# H19R1_Backend.net
KiCad netlist of a schematic drawn in Altium Designer
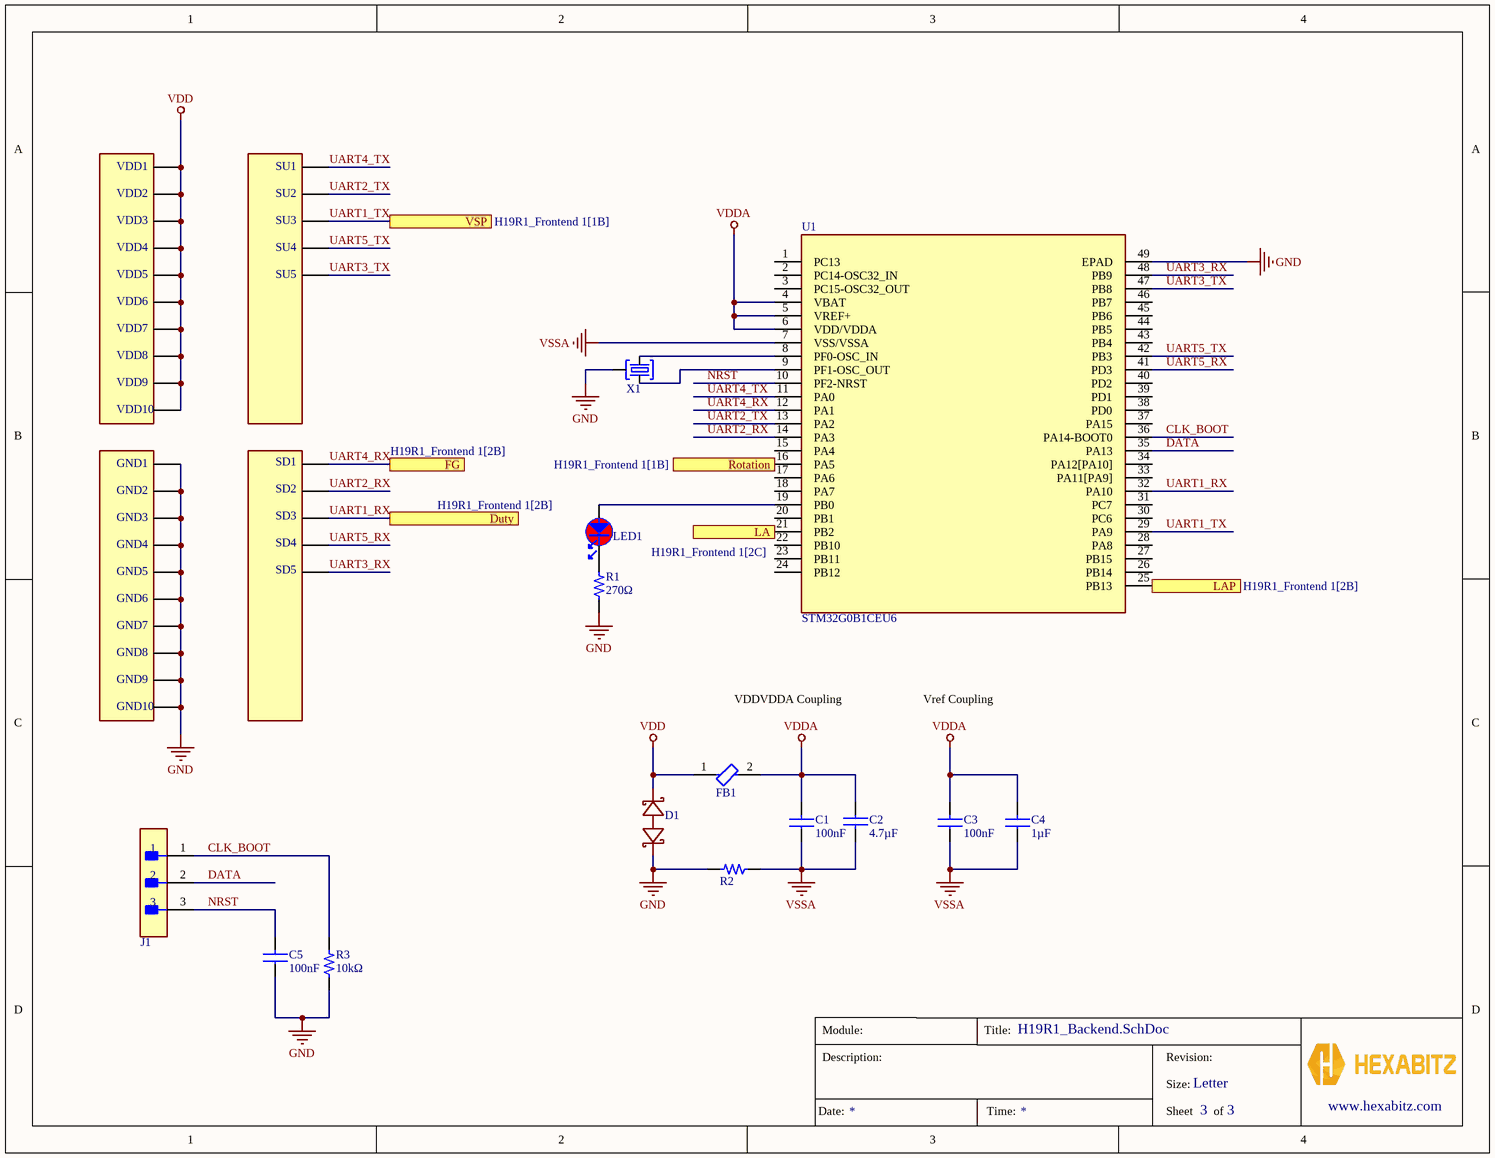
[diagram p0: H19R1_Backend.SchDoc]

(export (version "E")
  (design (tool "Eeschema 10.0.6"))
  (components
    (comp (ref "C1")
      (value "100nF")
      (footprint "C0603")
      (fields
        (field (name "MANUFACTURER") "Samsung Electro-Mechanics")
        (field (name "MANUFACTURER PART NUMBER") "CL10B104KA8NNNC")
        (field (name "TOLERANCE") "10%")
      )
      (libsource (lib "Hexabitz Altium Library") (part "generic Capacitor"))
    )
    (comp (ref "C2")
      (value "4.7µF")
      (footprint "C0805")
      (fields
        (field (name "MANUFACTURER") "Samsung Electro-Mechanics")
        (field (name "MANUFACTURER PART NUMBER") "CL21X475KAQNNNE")
        (field (name "TOLERANCE") "10%")
      )
      (libsource (lib "Hexabitz Altium Library") (part "generic Capacitor"))
    )
    (comp (ref "C3")
      (value "100nF")
      (footprint "C0603")
      (fields
        (field (name "MANUFACTURER") "Samsung Electro-Mechanics")
        (field (name "MANUFACTURER PART NUMBER") "CL10B104KA8NNNC")
        (field (name "TOLERANCE") "10%")
      )
      (libsource (lib "Hexabitz Altium Library") (part "generic Capacitor"))
    )
    (comp (ref "C4")
      (value "1µF")
      (footprint "C0805")
      (description "Ceramic Capacitor, Ceramic, 16V, 10% +Tol, 10% -Tol, X7R, 15% TC, 1uF, Surface Mount, 0805")
      (fields
        (field (name "MANUFACTURER") "Yageo Group")
        (field (name "MANUFACTURER PART NUMBER") "CC0805KKX7R7BB105")
      )
      (libsource (lib "Hexabitz Altium Library") (part "generic Capacitor"))
    )
    (comp (ref "C5")
      (value "100nF")
      (footprint "C0603")
      (fields
        (field (name "MANUFACTURER") "Samsung Electro-Mechanics")
        (field (name "MANUFACTURER PART NUMBER") "CL10B104KA8NNNC")
        (field (name "TOLERANCE") "10%")
      )
      (libsource (lib "Hexabitz Altium Library") (part "generic Capacitor"))
    )
    (comp (ref "D1")
      (value "CDSOD323-T03SC")
      (footprint "SOD2513X114N")
      (description "A 3V, 350W, bi-directional, standard capacitance, SOD323 pkg TVS Diode ¦ Bourns CDSOD323-T03SC")
      (fields (field (name "MANUFACTURER") "Bourns"))
      (libsource (lib "Hexabitz Altium Library") (part "CDSOD323-T03SC"))
    )
    (comp (ref "FB1")
      (value "MMZ1608Y300B")
      (footprint "FP-MMZ1608-0_8-MFG")
      (description "Ferrite Beads 0603 30ohms 1500mA Signal Line AEC-Q200")
      (fields
        (field (name "MANUFACTURER") "TDK")
        (field (name "MANUFACTURER PART NUMBER") "MMZ1608Y300BTD25")
      )
      (libsource (lib "Hexabitz Altium Library") (part "MMZ1608Y300B"))
    )
    (comp (ref "GND1")
      (value "HEXABIT_UART_PORT")
      (footprint "HEXABIT_POWER_PORT_D")
      (libsource (lib "hexabitz_connectors.Library") (part "HEXABIT_POWER_PORT_D"))
    )
    (comp (ref "GND2")
      (value "HEXABIT_UART_PORT")
      (footprint "HEXABIT_POWER_PORT_D")
      (libsource (lib "hexabitz_connectors.Library") (part "HEXABIT_POWER_PORT_D"))
    )
    (comp (ref "GND3")
      (value "HEXABIT_UART_PORT")
      (footprint "HEXABIT_POWER_PORT_D_300R")
      (libsource (lib "hexabitz_connectors.Library") (part "HEXABIT_POWER_PORT_D_300R"))
    )
    (comp (ref "GND4")
      (value "HEXABIT_UART_PORT")
      (footprint "HEXABIT_POWER_PORT_D")
      (libsource (lib "hexabitz_connectors.Library") (part "HEXABIT_POWER_PORT_D"))
    )
    (comp (ref "GND5")
      (value "HEXABIT_UART_PORT")
      (footprint "HEXABIT_POWER_PORT_D")
      (libsource (lib "hexabitz_connectors.Library") (part "HEXABIT_POWER_PORT_D"))
    )
    (comp (ref "GND6")
      (value "HEXABIT_UART_PORT")
      (footprint "HEXABIT_POWER_PORT_D")
      (libsource (lib "hexabitz_connectors.Library") (part "HEXABIT_POWER_PORT_D"))
    )
    (comp (ref "GND7")
      (value "HEXABIT_UART_PORT")
      (footprint "HEXABIT_POWER_PORT_D")
      (libsource (lib "hexabitz_connectors.Library") (part "HEXABIT_POWER_PORT_D"))
    )
    (comp (ref "GND8")
      (value "HEXABIT_UART_PORT")
      (footprint "HEXABIT_POWER_PORT_D_300L")
      (libsource (lib "hexabitz_connectors.Library") (part "HEXABIT_POWER_PORT_D_300L"))
    )
    (comp (ref "GND9")
      (value "HEXABIT_UART_PORT")
      (footprint "HEXABIT_POWER_PORT_D")
      (libsource (lib "hexabitz_connectors.Library") (part "HEXABIT_POWER_PORT_D"))
    )
    (comp (ref "GND10")
      (value "HEXABIT_UART_PORT")
      (footprint "HEXABIT_POWER_PORT_D")
      (libsource (lib "hexabitz_connectors.Library") (part "HEXABIT_POWER_PORT_D"))
    )
    (comp (ref "J1")
      (value "TSW-103-14-G-S")
      (footprint "FP-TSW-103-14-G-S-MFG")
      (description "CONN HEADER VERT 3POS 2.54MM")
      (libsource (lib "Altium Content Vault") (part "cd3439d6ef35ae5d9b27ec4fdd3e828"))
    )
    (comp (ref "LED1")
      (value "VLMS1300-GS08")
      (footprint "FP-6_541-5092_01-4-MFG")
      (description "LED Uni-Color Super Red 639nm 2-Pin Chip 0603(1608Metric) T/R")
      (fields (field (name "MANUFACTURER") "Vishay Semiconductors"))
      (libsource (lib "Hexabitz Altium Library") (part "VLMS1300-GS08"))
    )
    (comp (ref "R1")
      (value "270Ω")
      (footprint "R0603")
      (description "Res Thick Film 0603 270 Ohm 5% 0.1W(1/10W) ±200ppm/C Pad SMD Automotive T/R")
      (fields
        (field (name "MANUFACTURER") "Panasonic")
        (field (name "MANUFACTURER PART NUMBER") "ERJ-3GEYJ271V")
      )
      (libsource (lib "Hexabitz Altium Library") (part "generic Resistor"))
    )
    (comp (ref "R2")
      (value "Manufacturer Part Number")
      (footprint "R0603")
      (libsource (lib "") (part "generic Resistor_2"))
    )
    (comp (ref "R3")
      (value "10kΩ")
      (footprint "R0603")
      (description "100mW Thick Film Resistors ±100ppm/℃ ±1% 10kΩ 0603 Chip Resistor - Surface Mount ROHS")
      (fields
        (field (name "MANUFACTURER") "Yageo Group")
        (field (name "MANUFACTURER PART NUMBER") "RC0603FR-0710KL")
      )
      (libsource (lib "") (part "generic Resistor_1"))
    )
    (comp (ref "SD1")
      (value "HEXABIT_UART_PORT")
      (footprint "HEXABIT_UART_PORT_D")
      (libsource (lib "hexabitz_connectors.Library") (part "HEXABIT_UART_PORT_D"))
    )
    (comp (ref "SD2")
      (value "HEXABIT_UART_PORT")
      (footprint "HEXABIT_UART_PORT_D")
      (libsource (lib "hexabitz_connectors.Library") (part "HEXABIT_UART_PORT_D"))
    )
    (comp (ref "SD3")
      (value "HEXABIT_UART_PORT")
      (footprint "HEXABIT_UART_PORT_D")
      (libsource (lib "hexabitz_connectors.Library") (part "HEXABIT_UART_PORT_D"))
    )
    (comp (ref "SD4")
      (value "HEXABIT_UART_PORT")
      (footprint "HEXABIT_UART_PORT_D")
      (libsource (lib "hexabitz_connectors.Library") (part "HEXABIT_UART_PORT_D"))
    )
    (comp (ref "SD5")
      (value "HEXABIT_UART_PORT")
      (footprint "HEXABIT_UART_PORT_D")
      (libsource (lib "hexabitz_connectors.Library") (part "HEXABIT_UART_PORT_D"))
    )
    (comp (ref "SU1")
      (value "HEXABIT_UART_PORT")
      (footprint "HEXABIT_UART_PORT_U")
      (libsource (lib "hexabitz_connectors.Library") (part "HEXABIT_UART_PORT_U"))
    )
    (comp (ref "SU2")
      (value "HEXABIT_UART_PORT")
      (footprint "HEXABIT_UART_PORT_U")
      (libsource (lib "hexabitz_connectors.Library") (part "HEXABIT_UART_PORT_U"))
    )
    (comp (ref "SU3")
      (value "HEXABIT_UART_PORT")
      (footprint "HEXABIT_UART_PORT_U")
      (libsource (lib "hexabitz_connectors.Library") (part "HEXABIT_UART_PORT_U"))
    )
    (comp (ref "SU4")
      (value "HEXABIT_UART_PORT")
      (footprint "HEXABIT_UART_PORT_U")
      (libsource (lib "hexabitz_connectors.Library") (part "HEXABIT_UART_PORT_U"))
    )
    (comp (ref "SU5")
      (value "HEXABIT_UART_PORT")
      (footprint "HEXABIT_UART_PORT_U")
      (libsource (lib "hexabitz_connectors.Library") (part "HEXABIT_UART_PORT_U"))
    )
    (comp (ref "U1")
      (value "STM32G0B1CEU6")
      (footprint "QFN50P700X700X65-49N-D")
      (description "MCU 32-bit ARM Cortex M0+ RISC 512KB Flash 1.8V/2.5V/3.3V 48-Pin UFQFPN EP Tray")
      (fields
        (field (name "MANUFACTURER") "STMicroelectronics")
        (field (name "MANUFACTURER PART NUMBER") "STM32G0B1CEU6")
      )
      (libsource (lib "Hexabitz Altium Library") (part "STM32G0B1CEU6"))
    )
    (comp (ref "VDD1")
      (value "HEXABIT_UART_PORT")
      (footprint "HEXABIT_POWER_PORT_U")
      (libsource (lib "hexabitz_connectors.Library") (part "HEXABIT_POWER_PORT_U"))
    )
    (comp (ref "VDD2")
      (value "HEXABIT_UART_PORT")
      (footprint "HEXABIT_POWER_PORT_U")
      (libsource (lib "hexabitz_connectors.Library") (part "HEXABIT_POWER_PORT_U"))
    )
    (comp (ref "VDD3")
      (value "HEXABIT_UART_PORT")
      (footprint "HEXABIT_POWER_PORT_U_300R")
      (libsource (lib "hexabitz_connectors.Library") (part "HEXABIT_POWER_PORT_U_300R"))
    )
    (comp (ref "VDD4")
      (value "HEXABIT_UART_PORT")
      (footprint "HEXABIT_POWER_PORT_U")
      (libsource (lib "hexabitz_connectors.Library") (part "HEXABIT_POWER_PORT_U"))
    )
    (comp (ref "VDD5")
      (value "HEXABIT_UART_PORT")
      (footprint "HEXABIT_POWER_PORT_U")
      (libsource (lib "hexabitz_connectors.Library") (part "HEXABIT_POWER_PORT_U"))
    )
    (comp (ref "VDD6")
      (value "HEXABIT_UART_PORT")
      (footprint "HEXABIT_POWER_PORT_U")
      (libsource (lib "hexabitz_connectors.Library") (part "HEXABIT_POWER_PORT_U"))
    )
    (comp (ref "VDD7")
      (value "HEXABIT_UART_PORT")
      (footprint "HEXABIT_POWER_PORT_U")
      (libsource (lib "hexabitz_connectors.Library") (part "HEXABIT_POWER_PORT_U"))
    )
    (comp (ref "VDD8")
      (value "HEXABIT_UART_PORT")
      (footprint "HEXABIT_POWER_PORT_U_300L")
      (libsource (lib "hexabitz_connectors.Library") (part "HEXABIT_POWER_PORT_U_300L"))
    )
    (comp (ref "VDD9")
      (value "HEXABIT_UART_PORT")
      (footprint "HEXABIT_POWER_PORT_U")
      (libsource (lib "hexabitz_connectors.Library") (part "HEXABIT_POWER_PORT_U"))
    )
    (comp (ref "VDD10")
      (value "HEXABIT_UART_PORT")
      (footprint "HEXABIT_POWER_PORT_U")
      (libsource (lib "hexabitz_connectors.Library") (part "HEXABIT_POWER_PORT_U"))
    )
    (comp (ref "X1")
      (value "CSTCE8M00G52Z-R0")
      (footprint "XTALL_CSTCE8M00G52")
      (description "Ceramic Resonator 8MHz ±0.5% (Tol) ±0.2% (Stability) 10pF 40Ohm 3-Pin CSMD T/R")
      (fields (field (name "MANUFACTURER") "Murata") (field (name "TOLERANCE") "0.5%"))
      (libsource (lib "Hexabitz Altium Library") (part "CSTCE8M00G52Z-R0"))
    )
  )
  (nets
    (net (code "1") (name "/CLK_BOOT") (class "Default")
      (node (ref "J1") (pin "1") (pinfunction "1_1") (pintype "passive"))
      (node (ref "R3") (pin "1") (pinfunction "1_1") (pintype "passive"))
      (node (ref "U1") (pin "36") (pinfunction "PA14-BOOT0_36") (pintype "passive"))
    )
    (net (code "2") (name "/DATA") (class "Default")
      (node (ref "J1") (pin "2") (pinfunction "2_2") (pintype "passive"))
      (node (ref "U1") (pin "35") (pinfunction "PA13_35") (pintype "passive"))
    )
    (net (code "3") (name "/LA") (class "Default")
      (node (ref "U1") (pin "21") (pinfunction "PB2_21") (pintype "passive"))
    )
    (net (code "4") (name "/LAP") (class "Default")
      (node (ref "U1") (pin "25") (pinfunction "PB13_25") (pintype "passive"))
    )
    (net (code "5") (name "/NRST") (class "Default")
      (node (ref "C5") (pin "2") (pinfunction "2_2") (pintype "passive"))
      (node (ref "J1") (pin "3") (pinfunction "3_3") (pintype "passive"))
      (node (ref "U1") (pin "10") (pinfunction "PF2-NRST_10") (pintype "passive"))
    )
    (net (code "6") (name "/Rotation") (class "Default")
      (node (ref "U1") (pin "16") (pinfunction "PA5_16") (pintype "passive"))
    )
    (net (code "7") (name "/UART1_RX") (class "Default")
      (node (ref "SD3") (pin "UART_D") (pinfunction "UART_D_UART_D") (pintype "passive"))
      (node (ref "U1") (pin "32") (pinfunction "PA10_32") (pintype "passive"))
    )
    (net (code "8") (name "/UART1_TX") (class "Default")
      (node (ref "SU3") (pin "UART_U") (pinfunction "UART_U_UART_U") (pintype "passive"))
      (node (ref "U1") (pin "29") (pinfunction "PA9_29") (pintype "passive"))
    )
    (net (code "9") (name "/UART2_RX") (class "Default")
      (node (ref "SD2") (pin "UART_D") (pinfunction "UART_D_UART_D") (pintype "passive"))
      (node (ref "U1") (pin "14") (pinfunction "PA3_14") (pintype "passive"))
    )
    (net (code "10") (name "/UART2_TX") (class "Default")
      (node (ref "SU2") (pin "UART_U") (pinfunction "UART_U_UART_U") (pintype "passive"))
      (node (ref "U1") (pin "13") (pinfunction "PA2_13") (pintype "passive"))
    )
    (net (code "11") (name "/UART3_RX") (class "Default")
      (node (ref "SD5") (pin "UART_D") (pinfunction "UART_D_UART_D") (pintype "passive"))
      (node (ref "U1") (pin "48") (pinfunction "PB9_48") (pintype "passive"))
    )
    (net (code "12") (name "/UART3_TX") (class "Default")
      (node (ref "SU5") (pin "UART_U") (pinfunction "UART_U_UART_U") (pintype "passive"))
      (node (ref "U1") (pin "47") (pinfunction "PB8_47") (pintype "passive"))
    )
    (net (code "13") (name "/UART4_RX") (class "Default")
      (node (ref "SD1") (pin "UART_D") (pinfunction "UART_D_UART_D") (pintype "passive"))
      (node (ref "U1") (pin "12") (pinfunction "PA1_12") (pintype "passive"))
    )
    (net (code "14") (name "/UART4_TX") (class "Default")
      (node (ref "SU1") (pin "UART_U") (pinfunction "UART_U_UART_U") (pintype "passive"))
      (node (ref "U1") (pin "11") (pinfunction "PA0_11") (pintype "passive"))
    )
    (net (code "15") (name "/UART5_RX") (class "Default")
      (node (ref "SD4") (pin "UART_D") (pinfunction "UART_D_UART_D") (pintype "passive"))
      (node (ref "U1") (pin "41") (pinfunction "PD3_41") (pintype "passive"))
    )
    (net (code "16") (name "/UART5_TX") (class "Default")
      (node (ref "SU4") (pin "UART_U") (pinfunction "UART_U_UART_U") (pintype "passive"))
      (node (ref "U1") (pin "42") (pinfunction "PB3_42") (pintype "passive"))
    )
    (net (code "17") (name "GND") (class "Default")
      (node (ref "C5") (pin "1") (pinfunction "1_1") (pintype "passive"))
      (node (ref "D1") (pin "1") (pinfunction "A_1") (pintype "passive"))
      (node (ref "GND1") (pin "Pwr_D") (pinfunction "Pwr_D_Pwr_D") (pintype "passive"))
      (node (ref "GND10") (pin "Pwr_D") (pinfunction "Pwr_D_Pwr_D") (pintype "passive"))
      (node (ref "GND2") (pin "Pwr_D") (pinfunction "Pwr_D_Pwr_D") (pintype "passive"))
      (node (ref "GND3") (pin "Pwr_D") (pinfunction "Pwr_D_Pwr_D") (pintype "passive"))
      (node (ref "GND4") (pin "Pwr_D") (pinfunction "Pwr_D_Pwr_D") (pintype "passive"))
      (node (ref "GND5") (pin "Pwr_D") (pinfunction "Pwr_D_Pwr_D") (pintype "passive"))
      (node (ref "GND6") (pin "Pwr_D") (pinfunction "Pwr_D_Pwr_D") (pintype "passive"))
      (node (ref "GND7") (pin "Pwr_D") (pinfunction "Pwr_D_Pwr_D") (pintype "passive"))
      (node (ref "GND8") (pin "Pwr_D") (pinfunction "Pwr_D_Pwr_D") (pintype "passive"))
      (node (ref "GND9") (pin "Pwr_D") (pinfunction "Pwr_D_Pwr_D") (pintype "passive"))
      (node (ref "R1") (pin "1") (pinfunction "1_1") (pintype "passive"))
      (node (ref "R2") (pin "1") (pinfunction "1_1") (pintype "passive"))
      (node (ref "R3") (pin "2") (pinfunction "2_2") (pintype "passive"))
      (node (ref "U1") (pin "49") (pinfunction "EPAD_49") (pintype "passive"))
      (node (ref "X1") (pin "P$2") (pinfunction "2_P$2") (pintype "passive"))
    )
    (net (code "18") (name "Net-(LED1-Pad1)") (class "Default")
      (node (ref "LED1") (pin "1") (pintype "passive"))
      (node (ref "R1") (pin "2") (pinfunction "2_2") (pintype "passive"))
    )
    (net (code "19") (name "Net-(U1-PB0)") (class "Default")
      (node (ref "LED1") (pin "2") (pintype "passive"))
      (node (ref "U1") (pin "19") (pinfunction "PB0_19") (pintype "passive"))
    )
    (net (code "20") (name "Net-(U1-PF0-OSC_IN)") (class "Default")
      (node (ref "U1") (pin "8") (pinfunction "PF0-OSC_IN_8") (pintype "passive"))
      (node (ref "X1") (pin "P$3") (pinfunction "3_P$3") (pintype "passive"))
    )
    (net (code "21") (name "Net-(U1-PF1-OSC_OUT)") (class "Default")
      (node (ref "U1") (pin "9") (pinfunction "PF1-OSC_OUT_9") (pintype "passive"))
      (node (ref "X1") (pin "P$1") (pinfunction "1_P$1") (pintype "passive"))
    )
    (net (code "22") (name "VDD") (class "Default")
      (node (ref "D1") (pin "2") (pinfunction "C_2") (pintype "passive"))
      (node (ref "FB1") (pin "1") (pinfunction "1_1") (pintype "passive"))
      (node (ref "VDD1") (pin "Pwr_U") (pinfunction "Pwr_U_Pwr_U") (pintype "passive"))
      (node (ref "VDD10") (pin "Pwr_U") (pinfunction "Pwr_U_Pwr_U") (pintype "passive"))
      (node (ref "VDD2") (pin "Pwr_U") (pinfunction "Pwr_U_Pwr_U") (pintype "passive"))
      (node (ref "VDD3") (pin "Pwr_U") (pinfunction "Pwr_U_Pwr_U") (pintype "passive"))
      (node (ref "VDD4") (pin "Pwr_U") (pinfunction "Pwr_U_Pwr_U") (pintype "passive"))
      (node (ref "VDD5") (pin "Pwr_U") (pinfunction "Pwr_U_Pwr_U") (pintype "passive"))
      (node (ref "VDD6") (pin "Pwr_U") (pinfunction "Pwr_U_Pwr_U") (pintype "passive"))
      (node (ref "VDD7") (pin "Pwr_U") (pinfunction "Pwr_U_Pwr_U") (pintype "passive"))
      (node (ref "VDD8") (pin "Pwr_U") (pinfunction "Pwr_U_Pwr_U") (pintype "passive"))
      (node (ref "VDD9") (pin "Pwr_U") (pinfunction "Pwr_U_Pwr_U") (pintype "passive"))
    )
    (net (code "23") (name "VDDA") (class "Default")
      (node (ref "C1") (pin "2") (pinfunction "2_2") (pintype "passive"))
      (node (ref "C2") (pin "1") (pinfunction "1_1") (pintype "passive"))
      (node (ref "C3") (pin "2") (pinfunction "2_2") (pintype "passive"))
      (node (ref "C4") (pin "2") (pinfunction "2_2") (pintype "passive"))
      (node (ref "FB1") (pin "2") (pinfunction "2_2") (pintype "passive"))
      (node (ref "U1") (pin "4") (pinfunction "VBAT_4") (pintype "passive"))
      (node (ref "U1") (pin "5") (pinfunction "VREF+_5") (pintype "passive"))
      (node (ref "U1") (pin "6") (pinfunction "VDD/VDDA_6") (pintype "passive"))
    )
    (net (code "24") (name "VSSA") (class "Default")
      (node (ref "C1") (pin "1") (pinfunction "1_1") (pintype "passive"))
      (node (ref "C2") (pin "2") (pinfunction "2_2") (pintype "passive"))
      (node (ref "C3") (pin "1") (pinfunction "1_1") (pintype "passive"))
      (node (ref "C4") (pin "1") (pinfunction "1_1") (pintype "passive"))
      (node (ref "R2") (pin "2") (pinfunction "2_2") (pintype "passive"))
      (node (ref "U1") (pin "7") (pinfunction "VSS/VSSA_7") (pintype "passive"))
    )
    (net (code "25") (name "unconnected-(U1-PA4-Pad15)") (class "Default")
      (node (ref "U1") (pin "15") (pinfunction "PA4_15") (pintype "passive"))
    )
    (net (code "26") (name "unconnected-(U1-PA6-Pad17)") (class "Default")
      (node (ref "U1") (pin "17") (pinfunction "PA6_17") (pintype "passive"))
    )
    (net (code "27") (name "unconnected-(U1-PA7-Pad18)") (class "Default")
      (node (ref "U1") (pin "18") (pinfunction "PA7_18") (pintype "passive"))
    )
    (net (code "28") (name "unconnected-(U1-PA8-Pad28)") (class "Default")
      (node (ref "U1") (pin "28") (pinfunction "PA8_28") (pintype "passive"))
    )
    (net (code "29") (name "unconnected-(U1-PA11[PA9]-Pad33)") (class "Default")
      (node (ref "U1") (pin "33") (pinfunction "PA11[PA9]_33") (pintype "passive"))
    )
    (net (code "30") (name "unconnected-(U1-PA12[PA10]-Pad34)") (class "Default")
      (node (ref "U1") (pin "34") (pinfunction "PA12[PA10]_34") (pintype "passive"))
    )
    (net (code "31") (name "unconnected-(U1-PA15-Pad37)") (class "Default")
      (node (ref "U1") (pin "37") (pinfunction "PA15_37") (pintype "passive"))
    )
    (net (code "32") (name "unconnected-(U1-PB1-Pad20)") (class "Default")
      (node (ref "U1") (pin "20") (pinfunction "PB1_20") (pintype "passive"))
    )
    (net (code "33") (name "unconnected-(U1-PB4-Pad43)") (class "Default")
      (node (ref "U1") (pin "43") (pinfunction "PB4_43") (pintype "passive"))
    )
    (net (code "34") (name "unconnected-(U1-PB5-Pad44)") (class "Default")
      (node (ref "U1") (pin "44") (pinfunction "PB5_44") (pintype "passive"))
    )
    (net (code "35") (name "unconnected-(U1-PB6-Pad45)") (class "Default")
      (node (ref "U1") (pin "45") (pinfunction "PB6_45") (pintype "passive"))
    )
    (net (code "36") (name "unconnected-(U1-PB7-Pad46)") (class "Default")
      (node (ref "U1") (pin "46") (pinfunction "PB7_46") (pintype "passive"))
    )
    (net (code "37") (name "unconnected-(U1-PB10-Pad22)") (class "Default")
      (node (ref "U1") (pin "22") (pinfunction "PB10_22") (pintype "passive"))
    )
    (net (code "38") (name "unconnected-(U1-PB11-Pad23)") (class "Default")
      (node (ref "U1") (pin "23") (pinfunction "PB11_23") (pintype "passive"))
    )
    (net (code "39") (name "unconnected-(U1-PB12-Pad24)") (class "Default")
      (node (ref "U1") (pin "24") (pinfunction "PB12_24") (pintype "passive"))
    )
    (net (code "40") (name "unconnected-(U1-PB14-Pad26)") (class "Default")
      (node (ref "U1") (pin "26") (pinfunction "PB14_26") (pintype "passive"))
    )
    (net (code "41") (name "unconnected-(U1-PB15-Pad27)") (class "Default")
      (node (ref "U1") (pin "27") (pinfunction "PB15_27") (pintype "passive"))
    )
    (net (code "42") (name "unconnected-(U1-PC6-Pad30)") (class "Default")
      (node (ref "U1") (pin "30") (pinfunction "PC6_30") (pintype "passive"))
    )
    (net (code "43") (name "unconnected-(U1-PC7-Pad31)") (class "Default")
      (node (ref "U1") (pin "31") (pinfunction "PC7_31") (pintype "passive"))
    )
    (net (code "44") (name "unconnected-(U1-PC13-Pad1)") (class "Default")
      (node (ref "U1") (pin "1") (pinfunction "PC13_1") (pintype "passive"))
    )
    (net (code "45") (name "unconnected-(U1-PC14-OSC32_IN-Pad2)") (class "Default")
      (node (ref "U1") (pin "2") (pinfunction "PC14-OSC32_IN_2") (pintype "passive"))
    )
    (net (code "46") (name "unconnected-(U1-PC15-OSC32_OUT-Pad3)") (class "Default")
      (node (ref "U1") (pin "3") (pinfunction "PC15-OSC32_OUT_3") (pintype "passive"))
    )
    (net (code "47") (name "unconnected-(U1-PD0-Pad38)") (class "Default")
      (node (ref "U1") (pin "38") (pinfunction "PD0_38") (pintype "passive"))
    )
    (net (code "48") (name "unconnected-(U1-PD1-Pad39)") (class "Default")
      (node (ref "U1") (pin "39") (pinfunction "PD1_39") (pintype "passive"))
    )
    (net (code "49") (name "unconnected-(U1-PD2-Pad40)") (class "Default")
      (node (ref "U1") (pin "40") (pinfunction "PD2_40") (pintype "passive"))
    )
  )
)
